# rc2014_ADS1220.net
KiCad netlist of a schematic drawn in EAGLE
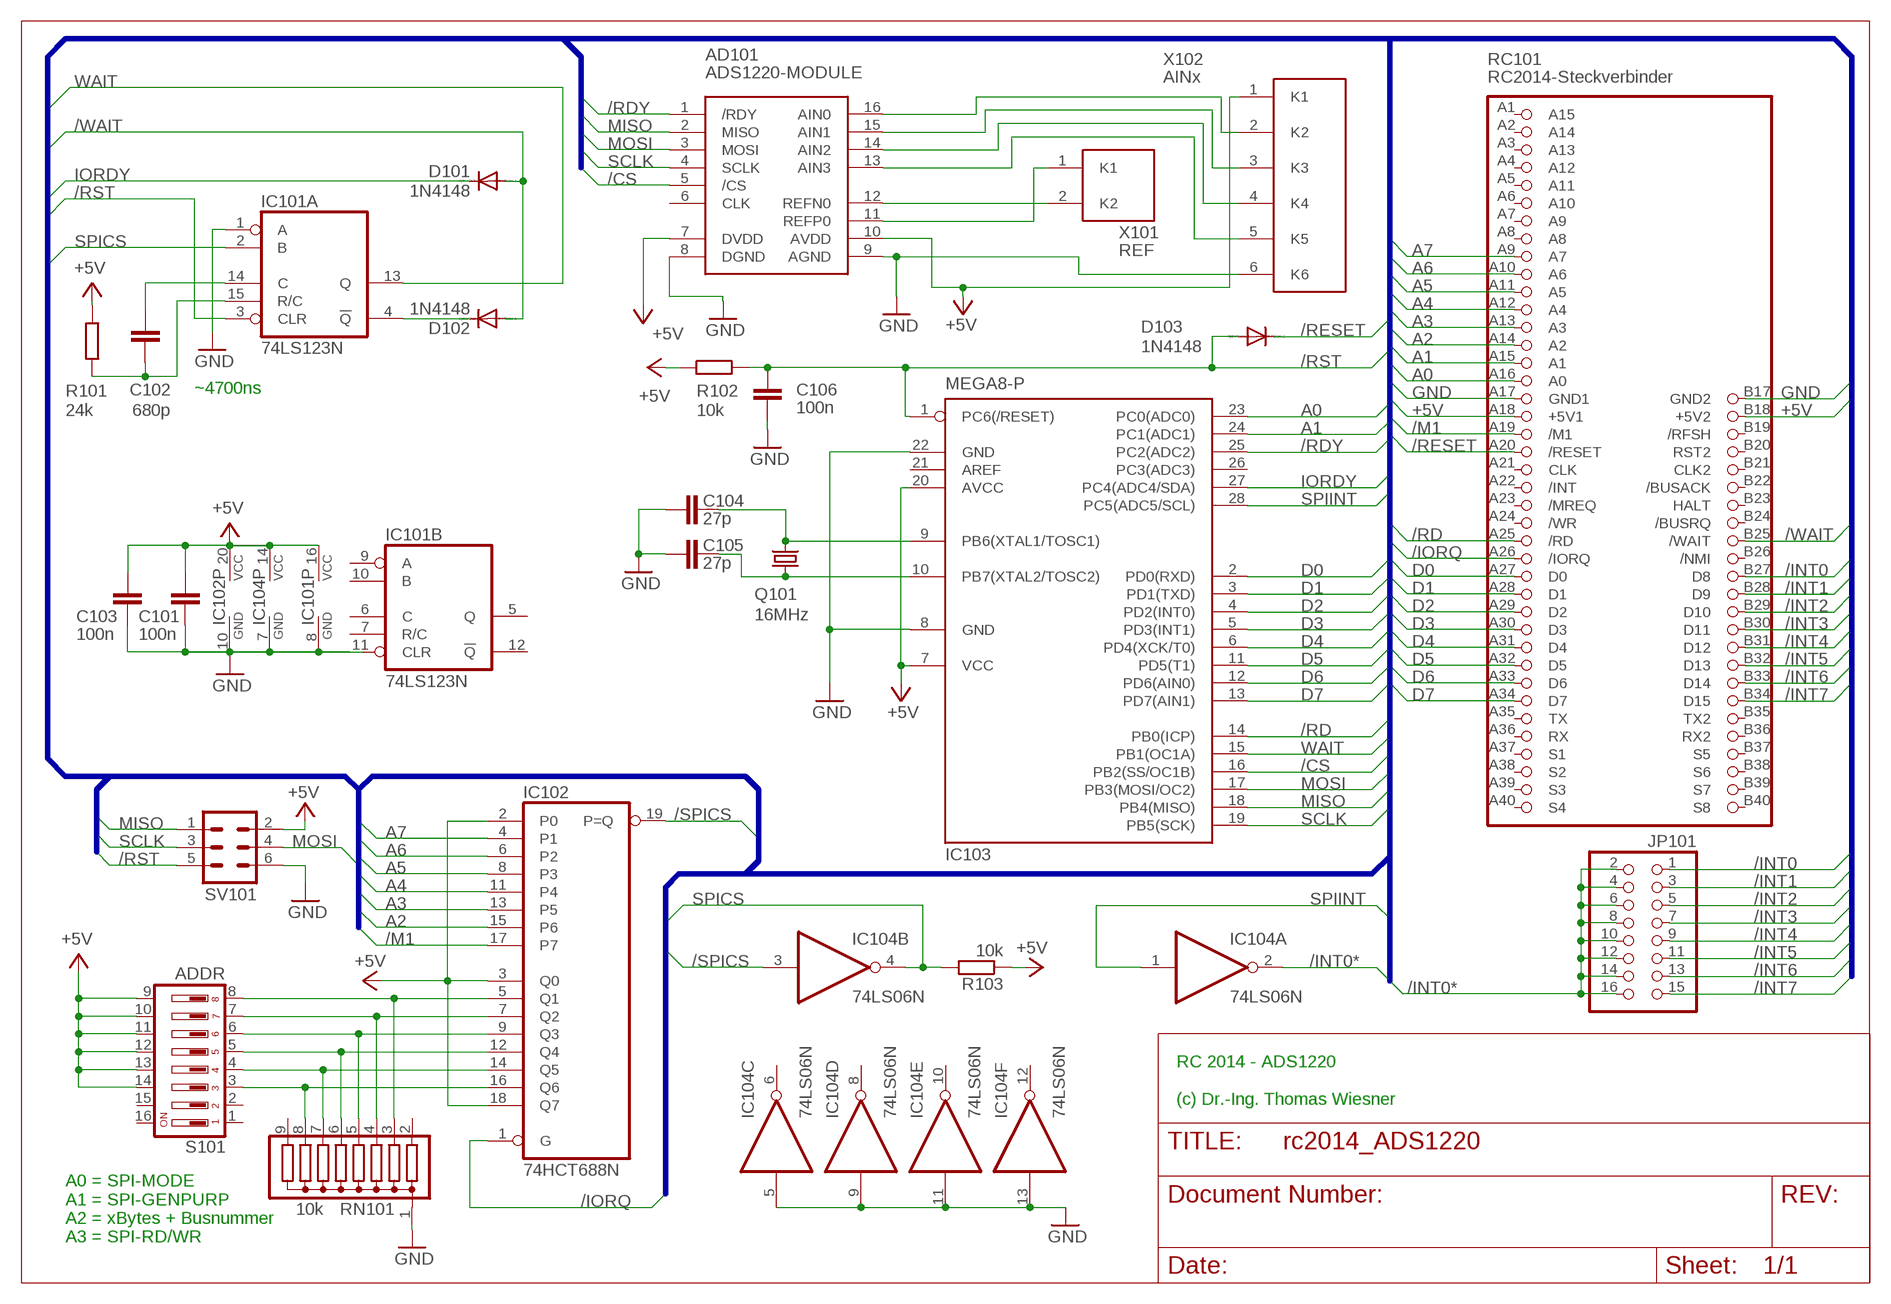
[diagram p0: schematic, sheet 1]

(export (version "E")
  (design (tool "Eeschema 10.0.6"))
  (components
    (comp (ref "AD101")
      (value "ADS1220-MODULE")
      (footprint "eagle-import:ADS1220-MOD")
      (libsource (lib "eagle-import") (part "ADS1220-MODULE"))
    )
    (comp (ref "C101")
      (value "100n")
      (footprint "eagle-import:C025-025X050")
      (libsource (lib "eagle-import") (part "C-EU025-025X050"))
    )
    (comp (ref "C102")
      (value "680p")
      (footprint "eagle-import:C025-025X050")
      (libsource (lib "eagle-import") (part "C-EU025-025X050"))
    )
    (comp (ref "C103")
      (value "100n")
      (footprint "eagle-import:C025-025X050")
      (libsource (lib "eagle-import") (part "C-EU025-025X050"))
    )
    (comp (ref "C104")
      (value "27p")
      (footprint "eagle-import:C025-025X050")
      (libsource (lib "eagle-import") (part "C-EU025-025X050"))
    )
    (comp (ref "C105")
      (value "27p")
      (footprint "eagle-import:C025-025X050")
      (libsource (lib "eagle-import") (part "C-EU025-025X050"))
    )
    (comp (ref "C106")
      (value "100n")
      (footprint "eagle-import:C025-025X050")
      (libsource (lib "eagle-import") (part "C-EU025-025X050"))
    )
    (comp (ref "D101")
      (value "1N4148")
      (footprint "eagle-import:DO35-10")
      (libsource (lib "eagle-import") (part "1N4148DO35-10"))
    )
    (comp (ref "D102")
      (value "1N4148")
      (footprint "eagle-import:DO35-10")
      (libsource (lib "eagle-import") (part "1N4148DO35-10"))
    )
    (comp (ref "D103")
      (value "1N4148")
      (footprint "eagle-import:DO35-10")
      (libsource (lib "eagle-import") (part "1N4148DO35-10"))
    )
    (comp (ref "IC101")
      (value "74LS123N")
      (footprint "eagle-import:DIL16")
      (libsource (lib "eagle-import") (part "74123NLS"))
    )
    (comp (ref "IC102")
      (value "74HCT688N")
      (footprint "eagle-import:DIL20")
      (libsource (lib "eagle-import") (part "74688NHCT"))
    )
    (comp (ref "IC103")
      (value "MEGA8-P")
      (footprint "eagle-import:DIL28-3")
      (libsource (lib "eagle-import") (part "MEGA8-P"))
    )
    (comp (ref "IC104")
      (value "74LS06N")
      (footprint "eagle-import:DIL14")
      (libsource (lib "eagle-import") (part "7406NLS"))
    )
    (comp (ref "JP101")
      (value "PINHD-2X8")
      (footprint "eagle-import:2X08")
      (libsource (lib "eagle-import") (part "PINHD-2X8"))
    )
    (comp (ref "Q101")
      (value "16MHz")
      (footprint "eagle-import:HC49U-V")
      (libsource (lib "eagle-import") (part "CRYSTALHC49U-V"))
    )
    (comp (ref "R101")
      (value "24k")
      (footprint "eagle-import:0207_10")
      (libsource (lib "eagle-import") (part "R-EU_0207/10"))
    )
    (comp (ref "R102")
      (value "10k")
      (footprint "eagle-import:0207_10")
      (libsource (lib "eagle-import") (part "R-EU_0207/10"))
    )
    (comp (ref "R103")
      (value "10k")
      (footprint "eagle-import:0207_10")
      (libsource (lib "eagle-import") (part "R-EU_0207/10"))
    )
    (comp (ref "RC101")
      (value "RC2014-Steckverbinder")
      (footprint "eagle-import:RC2014-STECKER")
      (libsource (lib "eagle-import") (part "RC2014STECKER"))
    )
    (comp (ref "RN101")
      (value "10k")
      (footprint "eagle-import:SIL9")
      (libsource (lib "eagle-import") (part "G08R"))
    )
    (comp (ref "S101")
      (value "ADDR")
      (footprint "eagle-import:DS-08")
      (fields (field (name "MPN") "DS08"))
      (libsource (lib "eagle-import") (part "DS08"))
    )
    (comp (ref "SV101")
      (value "ML6L")
      (footprint "eagle-import:ML6L")
      (libsource (lib "eagle-import") (part "ML6L"))
    )
    (comp (ref "X101")
      (value "REF")
      (footprint "eagle-import:AKL182-2")
      (libsource (lib "eagle-import") (part "AKL182-2"))
    )
    (comp (ref "X102")
      (value "AINx")
      (footprint "eagle-import:AKL182-6")
      (libsource (lib "eagle-import") (part "AKL182-6"))
    )
  )
  (nets
    (net (code "2") (name "+5V") (class "Default")
      (node (ref "AD101") (pin "10") (pinfunction "AVDD_10") (pintype "power_in"))
      (node (ref "AD101") (pin "7") (pinfunction "DVDD_7") (pintype "power_in"))
      (node (ref "C101") (pin "2") (pinfunction "2_2") (pintype "passive"))
      (node (ref "C103") (pin "2") (pinfunction "2_2") (pintype "passive"))
      (node (ref "IC101") (pin "16") (pinfunction "VCC_16") (pintype "power_in"))
      (node (ref "IC102") (pin "18") (pinfunction "Q7_18") (pintype "input"))
      (node (ref "IC102") (pin "2") (pinfunction "P0_2") (pintype "input"))
      (node (ref "IC102") (pin "20") (pinfunction "VCC_20") (pintype "power_in"))
      (node (ref "IC102") (pin "3") (pinfunction "Q0_3") (pintype "input"))
      (node (ref "IC103") (pin "20") (pinfunction "AVCC_20") (pintype "power_in"))
      (node (ref "IC103") (pin "7") (pinfunction "VCC_7") (pintype "power_in"))
      (node (ref "IC104") (pin "14") (pinfunction "VCC_14") (pintype "power_in"))
      (node (ref "R101") (pin "1") (pinfunction "1_1") (pintype "passive"))
      (node (ref "R102") (pin "1") (pinfunction "1_1") (pintype "passive"))
      (node (ref "R103") (pin "1") (pinfunction "1_1") (pintype "passive"))
      (node (ref "RC101") (pin "A18") (pinfunction "+5V1_A18") (pintype "passive"))
      (node (ref "RC101") (pin "B18") (pinfunction "+5V2_B18") (pintype "passive"))
      (node (ref "S101") (pin "10") (pinfunction "10_10") (pintype "passive"))
      (node (ref "S101") (pin "11") (pinfunction "11_11") (pintype "passive"))
      (node (ref "S101") (pin "12") (pinfunction "12_12") (pintype "passive"))
      (node (ref "S101") (pin "13") (pinfunction "13_13") (pintype "passive"))
      (node (ref "S101") (pin "14") (pinfunction "14_14") (pintype "passive"))
      (node (ref "S101") (pin "9") (pinfunction "9_9") (pintype "passive"))
      (node (ref "SV101") (pin "2") (pinfunction "2_2") (pintype "passive"))
      (node (ref "X102") (pin "1") (pinfunction "K1_1") (pintype "bidirectional"))
    )
    (net (code "3") (name "/A0") (class "Default")
      (node (ref "IC103") (pin "23") (pinfunction "PC0(ADC0)_23") (pintype "bidirectional"))
      (node (ref "RC101") (pin "A16") (pinfunction "A0_A16") (pintype "passive"))
    )
    (net (code "4") (name "/A1") (class "Default")
      (node (ref "IC103") (pin "24") (pinfunction "PC1(ADC1)_24") (pintype "bidirectional"))
      (node (ref "RC101") (pin "A15") (pinfunction "A1_A15") (pintype "passive"))
    )
    (net (code "5") (name "/A2") (class "Default")
      (node (ref "IC102") (pin "15") (pinfunction "P6_15") (pintype "input"))
      (node (ref "RC101") (pin "A14") (pinfunction "A2_A14") (pintype "passive"))
    )
    (net (code "6") (name "/A3") (class "Default")
      (node (ref "IC102") (pin "13") (pinfunction "P5_13") (pintype "input"))
      (node (ref "RC101") (pin "A13") (pinfunction "A3_A13") (pintype "passive"))
    )
    (net (code "7") (name "/A4") (class "Default")
      (node (ref "IC102") (pin "11") (pinfunction "P4_11") (pintype "input"))
      (node (ref "RC101") (pin "A12") (pinfunction "A4_A12") (pintype "passive"))
    )
    (net (code "8") (name "/A5") (class "Default")
      (node (ref "IC102") (pin "8") (pinfunction "P3_8") (pintype "input"))
      (node (ref "RC101") (pin "A11") (pinfunction "A5_A11") (pintype "passive"))
    )
    (net (code "9") (name "/A6") (class "Default")
      (node (ref "IC102") (pin "6") (pinfunction "P2_6") (pintype "input"))
      (node (ref "RC101") (pin "A10") (pinfunction "A6_A10") (pintype "passive"))
    )
    (net (code "10") (name "/A7") (class "Default")
      (node (ref "IC102") (pin "4") (pinfunction "P1_4") (pintype "input"))
      (node (ref "RC101") (pin "A9") (pinfunction "A7_A9") (pintype "passive"))
    )
    (net (code "11") (name "/D0") (class "Default")
      (node (ref "IC103") (pin "2") (pinfunction "PD0(RXD)_2") (pintype "bidirectional"))
      (node (ref "RC101") (pin "A27") (pinfunction "D0_A27") (pintype "passive"))
    )
    (net (code "12") (name "/D1") (class "Default")
      (node (ref "IC103") (pin "3") (pinfunction "PD1(TXD)_3") (pintype "bidirectional"))
      (node (ref "RC101") (pin "A28") (pinfunction "D1_A28") (pintype "passive"))
    )
    (net (code "13") (name "/D2") (class "Default")
      (node (ref "IC103") (pin "4") (pinfunction "PD2(INT0)_4") (pintype "bidirectional"))
      (node (ref "RC101") (pin "A29") (pinfunction "D2_A29") (pintype "passive"))
    )
    (net (code "14") (name "/D3") (class "Default")
      (node (ref "IC103") (pin "5") (pinfunction "PD3(INT1)_5") (pintype "bidirectional"))
      (node (ref "RC101") (pin "A30") (pinfunction "D3_A30") (pintype "passive"))
    )
    (net (code "15") (name "/D4") (class "Default")
      (node (ref "IC103") (pin "6") (pinfunction "PD4(XCK/T0)_6") (pintype "bidirectional"))
      (node (ref "RC101") (pin "A31") (pinfunction "D4_A31") (pintype "passive"))
    )
    (net (code "16") (name "/D5") (class "Default")
      (node (ref "IC103") (pin "11") (pinfunction "PD5(T1)_11") (pintype "bidirectional"))
      (node (ref "RC101") (pin "A32") (pinfunction "D5_A32") (pintype "passive"))
    )
    (net (code "17") (name "/D6") (class "Default")
      (node (ref "IC103") (pin "12") (pinfunction "PD6(AIN0)_12") (pintype "bidirectional"))
      (node (ref "RC101") (pin "A33") (pinfunction "D6_A33") (pintype "passive"))
    )
    (net (code "18") (name "/D7") (class "Default")
      (node (ref "IC103") (pin "13") (pinfunction "PD7(AIN1)_13") (pintype "bidirectional"))
      (node (ref "RC101") (pin "A34") (pinfunction "D7_A34") (pintype "passive"))
    )
    (net (code "19") (name "/IORDY") (class "Default")
      (node (ref "D101") (pin "C") (pinfunction "C_C") (pintype "passive"))
      (node (ref "IC103") (pin "27") (pinfunction "PC4(ADC4/SDA)_27") (pintype "bidirectional"))
    )
    (net (code "20") (name "/MISO") (class "Default")
      (node (ref "AD101") (pin "2") (pinfunction "MISO_2") (pintype "bidirectional"))
      (node (ref "IC103") (pin "18") (pinfunction "PB4(MISO)_18") (pintype "bidirectional"))
      (node (ref "SV101") (pin "1") (pinfunction "1_1") (pintype "passive"))
    )
    (net (code "21") (name "/MOSI") (class "Default")
      (node (ref "AD101") (pin "3") (pinfunction "MOSI_3") (pintype "bidirectional"))
      (node (ref "IC103") (pin "17") (pinfunction "PB3(MOSI/OC2)_17") (pintype "bidirectional"))
      (node (ref "SV101") (pin "4") (pinfunction "4_4") (pintype "passive"))
    )
    (net (code "22") (name "/SCLK") (class "Default")
      (node (ref "AD101") (pin "4") (pinfunction "SCLK_4") (pintype "bidirectional"))
      (node (ref "IC103") (pin "19") (pinfunction "PB5(SCK)_19") (pintype "bidirectional"))
      (node (ref "SV101") (pin "3") (pinfunction "3_3") (pintype "passive"))
    )
    (net (code "23") (name "/SPICS") (class "Default")
      (node (ref "IC101") (pin "2") (pinfunction "B_2") (pintype "input"))
      (node (ref "IC104") (pin "4") (pinfunction "O_4") (pintype "open_collector"))
      (node (ref "R103") (pin "2") (pinfunction "2_2") (pintype "passive"))
    )
    (net (code "24") (name "/SPIINT") (class "Default")
      (node (ref "IC103") (pin "28") (pinfunction "PC5(ADC5/SCL)_28") (pintype "bidirectional"))
      (node (ref "IC104") (pin "1") (pinfunction "I_1") (pintype "input"))
    )
    (net (code "25") (name "/WAIT") (class "Default")
      (node (ref "IC101") (pin "13") (pinfunction "Q_13") (pintype "output"))
      (node (ref "IC103") (pin "15") (pinfunction "PB1(OC1A)_15") (pintype "bidirectional"))
    )
    (net (code "27") (name "/{slash}CS") (class "Default")
      (node (ref "AD101") (pin "5") (pinfunction "/CS_5") (pintype "bidirectional"))
      (node (ref "IC103") (pin "16") (pinfunction "PB2(SS/OC1B)_16") (pintype "bidirectional"))
    )
    (net (code "28") (name "/{slash}INT0") (class "Default")
      (node (ref "JP101") (pin "1") (pinfunction "1_1") (pintype "passive"))
      (node (ref "RC101") (pin "B27") (pinfunction "D8_B27") (pintype "passive"))
    )
    (net (code "29") (name "/{slash}INT0*") (class "Default")
      (node (ref "IC104") (pin "2") (pinfunction "O_2") (pintype "open_collector"))
      (node (ref "JP101") (pin "10") (pinfunction "10_10") (pintype "passive"))
      (node (ref "JP101") (pin "12") (pinfunction "12_12") (pintype "passive"))
      (node (ref "JP101") (pin "14") (pinfunction "14_14") (pintype "passive"))
      (node (ref "JP101") (pin "16") (pinfunction "16_16") (pintype "passive"))
      (node (ref "JP101") (pin "2") (pinfunction "2_2") (pintype "passive"))
      (node (ref "JP101") (pin "4") (pinfunction "4_4") (pintype "passive"))
      (node (ref "JP101") (pin "6") (pinfunction "6_6") (pintype "passive"))
      (node (ref "JP101") (pin "8") (pinfunction "8_8") (pintype "passive"))
    )
    (net (code "30") (name "/{slash}INT1") (class "Default")
      (node (ref "JP101") (pin "3") (pinfunction "3_3") (pintype "passive"))
      (node (ref "RC101") (pin "B28") (pinfunction "D9_B28") (pintype "passive"))
    )
    (net (code "31") (name "/{slash}INT2") (class "Default")
      (node (ref "JP101") (pin "5") (pinfunction "5_5") (pintype "passive"))
      (node (ref "RC101") (pin "B29") (pinfunction "D10_B29") (pintype "passive"))
    )
    (net (code "32") (name "/{slash}INT3") (class "Default")
      (node (ref "JP101") (pin "7") (pinfunction "7_7") (pintype "passive"))
      (node (ref "RC101") (pin "B30") (pinfunction "D11_B30") (pintype "passive"))
    )
    (net (code "33") (name "/{slash}INT4") (class "Default")
      (node (ref "JP101") (pin "9") (pinfunction "9_9") (pintype "passive"))
      (node (ref "RC101") (pin "B31") (pinfunction "D12_B31") (pintype "passive"))
    )
    (net (code "34") (name "/{slash}INT5") (class "Default")
      (node (ref "JP101") (pin "11") (pinfunction "11_11") (pintype "passive"))
      (node (ref "RC101") (pin "B32") (pinfunction "D13_B32") (pintype "passive"))
    )
    (net (code "35") (name "/{slash}INT6") (class "Default")
      (node (ref "JP101") (pin "13") (pinfunction "13_13") (pintype "passive"))
      (node (ref "RC101") (pin "B33") (pinfunction "D14_B33") (pintype "passive"))
    )
    (net (code "36") (name "/{slash}INT7") (class "Default")
      (node (ref "JP101") (pin "15") (pinfunction "15_15") (pintype "passive"))
      (node (ref "RC101") (pin "B34") (pinfunction "D15_B34") (pintype "passive"))
    )
    (net (code "37") (name "/{slash}IORQ") (class "Default")
      (node (ref "IC102") (pin "1") (pinfunction "G_1") (pintype "input"))
      (node (ref "RC101") (pin "A26") (pinfunction "/IORQ_A26") (pintype "passive"))
    )
    (net (code "38") (name "/{slash}M1") (class "Default")
      (node (ref "IC102") (pin "17") (pinfunction "P7_17") (pintype "input"))
      (node (ref "RC101") (pin "A19") (pinfunction "/M1_A19") (pintype "passive"))
    )
    (net (code "39") (name "/{slash}RD") (class "Default")
      (node (ref "IC103") (pin "14") (pinfunction "PB0(ICP)_14") (pintype "bidirectional"))
      (node (ref "RC101") (pin "A25") (pinfunction "/RD_A25") (pintype "passive"))
    )
    (net (code "40") (name "/{slash}RDY") (class "Default")
      (node (ref "AD101") (pin "1") (pinfunction "/RDY_1") (pintype "bidirectional"))
      (node (ref "IC103") (pin "25") (pinfunction "PC2(ADC2)_25") (pintype "bidirectional"))
    )
    (net (code "41") (name "/{slash}RESET") (class "Default")
      (node (ref "D103") (pin "C") (pinfunction "C_C") (pintype "passive"))
      (node (ref "RC101") (pin "A20") (pinfunction "/RESET_A20") (pintype "passive"))
    )
    (net (code "42") (name "/{slash}RST") (class "Default")
      (node (ref "C106") (pin "2") (pinfunction "2_2") (pintype "passive"))
      (node (ref "D103") (pin "A") (pinfunction "A_A") (pintype "passive"))
      (node (ref "IC101") (pin "3") (pinfunction "CLR_3") (pintype "input"))
      (node (ref "IC103") (pin "1") (pinfunction "PC6(/RESET)_1") (pintype "bidirectional"))
      (node (ref "R102") (pin "2") (pinfunction "2_2") (pintype "passive"))
      (node (ref "SV101") (pin "5") (pinfunction "5_5") (pintype "passive"))
    )
    (net (code "43") (name "/{slash}SPICS") (class "Default")
      (node (ref "IC102") (pin "19") (pinfunction "P=Q_19") (pintype "output"))
      (node (ref "IC104") (pin "3") (pinfunction "I_3") (pintype "input"))
    )
    (net (code "44") (name "/{slash}WAIT") (class "Default")
      (node (ref "D101") (pin "A") (pinfunction "A_A") (pintype "passive"))
      (node (ref "D102") (pin "A") (pinfunction "A_A") (pintype "passive"))
      (node (ref "RC101") (pin "B25") (pinfunction "/WAIT_B25") (pintype "passive"))
    )
    (net (code "45") (name "GND") (class "Default")
      (node (ref "AD101") (pin "8") (pinfunction "DGND_8") (pintype "power_in"))
      (node (ref "AD101") (pin "9") (pinfunction "AGND_9") (pintype "power_in"))
      (node (ref "C101") (pin "1") (pinfunction "1_1") (pintype "passive"))
      (node (ref "C103") (pin "1") (pinfunction "1_1") (pintype "passive"))
      (node (ref "C104") (pin "2") (pinfunction "2_2") (pintype "passive"))
      (node (ref "C105") (pin "2") (pinfunction "2_2") (pintype "passive"))
      (node (ref "C106") (pin "1") (pinfunction "1_1") (pintype "passive"))
      (node (ref "IC101") (pin "1") (pinfunction "A_1") (pintype "input"))
      (node (ref "IC101") (pin "11") (pinfunction "CLR_11") (pintype "input"))
      (node (ref "IC101") (pin "8") (pinfunction "GND_8") (pintype "power_in"))
      (node (ref "IC102") (pin "10") (pinfunction "GND_10") (pintype "power_in"))
      (node (ref "IC103") (pin "22") (pinfunction "GND_22") (pintype "power_in"))
      (node (ref "IC103") (pin "8") (pinfunction "GND_8") (pintype "power_in"))
      (node (ref "IC104") (pin "11") (pinfunction "I_11") (pintype "input"))
      (node (ref "IC104") (pin "13") (pinfunction "I_13") (pintype "input"))
      (node (ref "IC104") (pin "5") (pinfunction "I_5") (pintype "input"))
      (node (ref "IC104") (pin "7") (pinfunction "GND_7") (pintype "power_in"))
      (node (ref "IC104") (pin "9") (pinfunction "I_9") (pintype "input"))
      (node (ref "RC101") (pin "A17") (pinfunction "GND1_A17") (pintype "passive"))
      (node (ref "RC101") (pin "B17") (pinfunction "GND2_B17") (pintype "passive"))
      (node (ref "RN101") (pin "1") (pinfunction "1_1") (pintype "passive"))
      (node (ref "SV101") (pin "6") (pinfunction "6_6") (pintype "passive"))
      (node (ref "X102") (pin "6") (pinfunction "K6_6") (pintype "bidirectional"))
    )
    (net (code "46") (name "Net-(AD101-AIN0)") (class "Default")
      (node (ref "AD101") (pin "16") (pinfunction "AIN0_16") (pintype "bidirectional"))
      (node (ref "X102") (pin "2") (pinfunction "K2_2") (pintype "bidirectional"))
    )
    (net (code "47") (name "Net-(AD101-AIN1)") (class "Default")
      (node (ref "AD101") (pin "15") (pinfunction "AIN1_15") (pintype "bidirectional"))
      (node (ref "X102") (pin "3") (pinfunction "K3_3") (pintype "bidirectional"))
    )
    (net (code "48") (name "Net-(AD101-AIN2)") (class "Default")
      (node (ref "AD101") (pin "14") (pinfunction "AIN2_14") (pintype "bidirectional"))
      (node (ref "X102") (pin "4") (pinfunction "K4_4") (pintype "bidirectional"))
    )
    (net (code "49") (name "Net-(AD101-AIN3)") (class "Default")
      (node (ref "AD101") (pin "13") (pinfunction "AIN3_13") (pintype "bidirectional"))
      (node (ref "X102") (pin "5") (pinfunction "K5_5") (pintype "bidirectional"))
    )
    (net (code "50") (name "Net-(AD101-REFN0)") (class "Default")
      (node (ref "AD101") (pin "12") (pinfunction "REFN0_12") (pintype "bidirectional"))
      (node (ref "X101") (pin "2") (pinfunction "K2_2") (pintype "bidirectional"))
    )
    (net (code "51") (name "Net-(AD101-REFP0)") (class "Default")
      (node (ref "AD101") (pin "11") (pinfunction "REFP0_11") (pintype "bidirectional"))
      (node (ref "X101") (pin "1") (pinfunction "K1_1") (pintype "bidirectional"))
    )
    (net (code "52") (name "Net-(IC101A-C)") (class "Default")
      (node (ref "C102") (pin "2") (pinfunction "2_2") (pintype "passive"))
      (node (ref "IC101") (pin "14") (pinfunction "C_14") (pintype "input"))
    )
    (net (code "53") (name "Net-(IC101A-R{slash}C)") (class "Default")
      (node (ref "C102") (pin "1") (pinfunction "1_1") (pintype "passive"))
      (node (ref "IC101") (pin "15") (pinfunction "R/C_15") (pintype "input"))
      (node (ref "R101") (pin "2") (pinfunction "2_2") (pintype "passive"))
    )
    (net (code "54") (name "Net-(IC101A-~{Q})") (class "Default")
      (node (ref "D102") (pin "C") (pinfunction "C_C") (pintype "passive"))
      (node (ref "IC101") (pin "4") (pinfunction "~{Q}_4") (pintype "output"))
    )
    (net (code "55") (name "Net-(IC102A-Q1)") (class "Default")
      (node (ref "IC102") (pin "5") (pinfunction "Q1_5") (pintype "input"))
      (node (ref "RN101") (pin "3") (pinfunction "3_3") (pintype "passive"))
      (node (ref "S101") (pin "8") (pinfunction "8_8") (pintype "passive"))
    )
    (net (code "56") (name "Net-(IC102A-Q2)") (class "Default")
      (node (ref "IC102") (pin "7") (pinfunction "Q2_7") (pintype "input"))
      (node (ref "RN101") (pin "4") (pinfunction "4_4") (pintype "passive"))
      (node (ref "S101") (pin "7") (pinfunction "7_7") (pintype "passive"))
    )
    (net (code "57") (name "Net-(IC102A-Q3)") (class "Default")
      (node (ref "IC102") (pin "9") (pinfunction "Q3_9") (pintype "input"))
      (node (ref "RN101") (pin "5") (pinfunction "5_5") (pintype "passive"))
      (node (ref "S101") (pin "6") (pinfunction "6_6") (pintype "passive"))
    )
    (net (code "58") (name "Net-(IC102A-Q4)") (class "Default")
      (node (ref "IC102") (pin "12") (pinfunction "Q4_12") (pintype "input"))
      (node (ref "RN101") (pin "6") (pinfunction "6_6") (pintype "passive"))
      (node (ref "S101") (pin "5") (pinfunction "5_5") (pintype "passive"))
    )
    (net (code "59") (name "Net-(IC102A-Q5)") (class "Default")
      (node (ref "IC102") (pin "14") (pinfunction "Q5_14") (pintype "input"))
      (node (ref "RN101") (pin "7") (pinfunction "7_7") (pintype "passive"))
      (node (ref "S101") (pin "4") (pinfunction "4_4") (pintype "passive"))
    )
    (net (code "60") (name "Net-(IC102A-Q6)") (class "Default")
      (node (ref "IC102") (pin "16") (pinfunction "Q6_16") (pintype "input"))
      (node (ref "RN101") (pin "8") (pinfunction "8_8") (pintype "passive"))
      (node (ref "S101") (pin "3") (pinfunction "3_3") (pintype "passive"))
    )
    (net (code "61") (name "Net-(IC103-PB6(XTAL1{slash}TOSC1))") (class "Default")
      (node (ref "C104") (pin "1") (pinfunction "1_1") (pintype "passive"))
      (node (ref "IC103") (pin "9") (pinfunction "PB6(XTAL1/TOSC1)_9") (pintype "bidirectional"))
      (node (ref "Q101") (pin "2") (pinfunction "2_2") (pintype "passive"))
    )
    (net (code "62") (name "Net-(IC103-PB7(XTAL2{slash}TOSC2))") (class "Default")
      (node (ref "C105") (pin "1") (pinfunction "1_1") (pintype "passive"))
      (node (ref "IC103") (pin "10") (pinfunction "PB7(XTAL2/TOSC2)_10") (pintype "bidirectional"))
      (node (ref "Q101") (pin "1") (pinfunction "1_1") (pintype "passive"))
    )
    (net (code "63") (name "unconnected-(AD101-CLK-Pad6)") (class "Default")
      (node (ref "AD101") (pin "6") (pinfunction "CLK_6") (pintype "bidirectional"))
    )
    (net (code "64") (name "unconnected-(IC101B-A-Pad9)") (class "Default")
      (node (ref "IC101") (pin "9") (pinfunction "A_9") (pintype "input"))
    )
    (net (code "65") (name "unconnected-(IC101B-B-Pad10)") (class "Default")
      (node (ref "IC101") (pin "10") (pinfunction "B_10") (pintype "input"))
    )
    (net (code "66") (name "unconnected-(IC101B-C-Pad6)") (class "Default")
      (node (ref "IC101") (pin "6") (pinfunction "C_6") (pintype "input"))
    )
    (net (code "67") (name "unconnected-(IC101B-Q-Pad5)") (class "Default")
      (node (ref "IC101") (pin "5") (pinfunction "Q_5") (pintype "output"))
    )
    (net (code "68") (name "unconnected-(IC101B-R{slash}C-Pad7)") (class "Default")
      (node (ref "IC101") (pin "7") (pinfunction "R/C_7") (pintype "input"))
    )
    (net (code "69") (name "unconnected-(IC101B-~{Q}-Pad12)") (class "Default")
      (node (ref "IC101") (pin "12") (pinfunction "~{Q}_12") (pintype "output"))
    )
    (net (code "70") (name "unconnected-(IC103-AREF-Pad21)") (class "Default")
      (node (ref "IC103") (pin "21") (pinfunction "AREF_21") (pintype "passive"))
    )
    (net (code "71") (name "unconnected-(IC103-PC3(ADC3)-Pad26)") (class "Default")
      (node (ref "IC103") (pin "26") (pinfunction "PC3(ADC3)_26") (pintype "bidirectional"))
    )
    (net (code "72") (name "unconnected-(IC104C-O-Pad6)") (class "Default")
      (node (ref "IC104") (pin "6") (pinfunction "O_6") (pintype "open_collector"))
    )
    (net (code "73") (name "unconnected-(IC104D-O-Pad8)") (class "Default")
      (node (ref "IC104") (pin "8") (pinfunction "O_8") (pintype "open_collector"))
    )
    (net (code "74") (name "unconnected-(IC104E-O-Pad10)") (class "Default")
      (node (ref "IC104") (pin "10") (pinfunction "O_10") (pintype "open_collector"))
    )
    (net (code "75") (name "unconnected-(IC104F-O-Pad12)") (class "Default")
      (node (ref "IC104") (pin "12") (pinfunction "O_12") (pintype "open_collector"))
    )
    (net (code "76") (name "unconnected-(RC101-A9-PadA7)") (class "Default")
      (node (ref "RC101") (pin "A7") (pinfunction "A9_A7") (pintype "passive"))
    )
    (net (code "77") (name "unconnected-(RC101-A10-PadA6)") (class "Default")
      (node (ref "RC101") (pin "A6") (pinfunction "A10_A6") (pintype "passive"))
    )
    (net (code "78") (name "unconnected-(RC101-A11-PadA5)") (class "Default")
      (node (ref "RC101") (pin "A5") (pinfunction "A11_A5") (pintype "passive"))
    )
    (net (code "79") (name "unconnected-(RC101-A12-PadA4)") (class "Default")
      (node (ref "RC101") (pin "A4") (pinfunction "A12_A4") (pintype "passive"))
    )
    (net (code "80") (name "unconnected-(RC101-A13-PadA3)") (class "Default")
      (node (ref "RC101") (pin "A3") (pinfunction "A13_A3") (pintype "passive"))
    )
    (net (code "81") (name "unconnected-(RC101-A14-PadA2)") (class "Default")
      (node (ref "RC101") (pin "A2") (pinfunction "A14_A2") (pintype "passive"))
    )
    (net (code "82") (name "unconnected-(RC101-A15-PadA1)") (class "Default")
      (node (ref "RC101") (pin "A1") (pinfunction "A15_A1") (pintype "passive"))
    )
    (net (code "83") (name "unconnected-(RC101-CLK-PadA21)") (class "Default")
      (node (ref "RC101") (pin "A21") (pinfunction "CLK_A21") (pintype "passive"))
    )
    (net (code "84") (name "unconnected-(RC101-CLK2-PadB21)") (class "Default")
      (node (ref "RC101") (pin "B21") (pinfunction "CLK2_B21") (pintype "passive"))
    )
    (net (code "85") (name "unconnected-(RC101-HALT-PadB23)") (class "Default")
      (node (ref "RC101") (pin "B23") (pinfunction "HALT_B23") (pintype "passive"))
    )
    (net (code "86") (name "unconnected-(RC101-PadA8)") (class "Default")
      (node (ref "RC101") (pin "A8") (pinfunction "A8_A8") (pintype "passive"))
    )
    (net (code "87") (name "unconnected-(RC101-RST2-PadB20)") (class "Default")
      (node (ref "RC101") (pin "B20") (pinfunction "RST2_B20") (pintype "passive"))
    )
    (net (code "88") (name "unconnected-(RC101-RX-PadA36)") (class "Default")
      (node (ref "RC101") (pin "A36") (pinfunction "RX_A36") (pintype "passive"))
    )
    (net (code "89") (name "unconnected-(RC101-RX2-PadB36)") (class "Default")
      (node (ref "RC101") (pin "B36") (pinfunction "RX2_B36") (pintype "passive"))
    )
    (net (code "90") (name "unconnected-(RC101-S1-PadA37)") (class "Default")
      (node (ref "RC101") (pin "A37") (pinfunction "S1_A37") (pintype "passive"))
    )
    (net (code "91") (name "unconnected-(RC101-S2-PadA38)") (class "Default")
      (node (ref "RC101") (pin "A38") (pinfunction "S2_A38") (pintype "passive"))
    )
    (net (code "92") (name "unconnected-(RC101-S3-PadA39)") (class "Default")
      (node (ref "RC101") (pin "A39") (pinfunction "S3_A39") (pintype "passive"))
    )
    (net (code "93") (name "unconnected-(RC101-S4-PadA40)") (class "Default")
      (node (ref "RC101") (pin "A40") (pinfunction "S4_A40") (pintype "passive"))
    )
    (net (code "94") (name "unconnected-(RC101-S5-PadB37)") (class "Default")
      (node (ref "RC101") (pin "B37") (pinfunction "S5_B37") (pintype "passive"))
    )
    (net (code "95") (name "unconnected-(RC101-S6-PadB38)") (class "Default")
      (node (ref "RC101") (pin "B38") (pinfunction "S6_B38") (pintype "passive"))
    )
    (net (code "96") (name "unconnected-(RC101-S7-PadB39)") (class "Default")
      (node (ref "RC101") (pin "B39") (pinfunction "S7_B39") (pintype "passive"))
    )
    (net (code "97") (name "unconnected-(RC101-S8-PadB40)") (class "Default")
      (node (ref "RC101") (pin "B40") (pinfunction "S8_B40") (pintype "passive"))
    )
    (net (code "98") (name "unconnected-(RC101-TX-PadA35)") (class "Default")
      (node (ref "RC101") (pin "A35") (pinfunction "TX_A35") (pintype "passive"))
    )
    (net (code "99") (name "unconnected-(RC101-TX2-PadB35)") (class "Default")
      (node (ref "RC101") (pin "B35") (pinfunction "TX2_B35") (pintype "passive"))
    )
    (net (code "100") (name "unconnected-(RC101-{slash}BUSACK-PadB22)") (class "Default")
      (node (ref "RC101") (pin "B22") (pinfunction "/BUSACK_B22") (pintype "passive"))
    )
    (net (code "101") (name "unconnected-(RC101-{slash}BUSRQ-PadB24)") (class "Default")
      (node (ref "RC101") (pin "B24") (pinfunction "/BUSRQ_B24") (pintype "passive"))
    )
    (net (code "102") (name "unconnected-(RC101-{slash}INT-PadA22)") (class "Default")
      (node (ref "RC101") (pin "A22") (pinfunction "/INT_A22") (pintype "passive"))
    )
    (net (code "103") (name "unconnected-(RC101-{slash}MREQ-PadA23)") (class "Default")
      (node (ref "RC101") (pin "A23") (pinfunction "/MREQ_A23") (pintype "passive"))
    )
    (net (code "104") (name "unconnected-(RC101-{slash}NMI-PadB26)") (class "Default")
      (node (ref "RC101") (pin "B26") (pinfunction "/NMI_B26") (pintype "passive"))
    )
    (net (code "105") (name "unconnected-(RC101-{slash}RFSH-PadB19)") (class "Default")
      (node (ref "RC101") (pin "B19") (pinfunction "/RFSH_B19") (pintype "passive"))
    )
    (net (code "106") (name "unconnected-(RC101-{slash}WR-PadA24)") (class "Default")
      (node (ref "RC101") (pin "A24") (pinfunction "/WR_A24") (pintype "passive"))
    )
    (net (code "107") (name "unconnected-(RN101-Pad2)") (class "Default")
      (node (ref "RN101") (pin "2") (pinfunction "2_2") (pintype "passive"))
    )
    (net (code "108") (name "unconnected-(RN101-Pad9)") (class "Default")
      (node (ref "RN101") (pin "9") (pinfunction "9_9") (pintype "passive"))
    )
    (net (code "109") (name "unconnected-(S101-Pad1)") (class "Default")
      (node (ref "S101") (pin "1") (pinfunction "1_1") (pintype "passive"))
    )
    (net (code "110") (name "unconnected-(S101-Pad2)") (class "Default")
      (node (ref "S101") (pin "2") (pinfunction "2_2") (pintype "passive"))
    )
    (net (code "111") (name "unconnected-(S101-Pad15)") (class "Default")
      (node (ref "S101") (pin "15") (pinfunction "15_15") (pintype "passive"))
    )
    (net (code "112") (name "unconnected-(S101-Pad16)") (class "Default")
      (node (ref "S101") (pin "16") (pinfunction "16_16") (pintype "passive"))
    )
  )
)
